# voltage_regulator_board.net
KiCad netlist of a schematic drawn in EAGLE
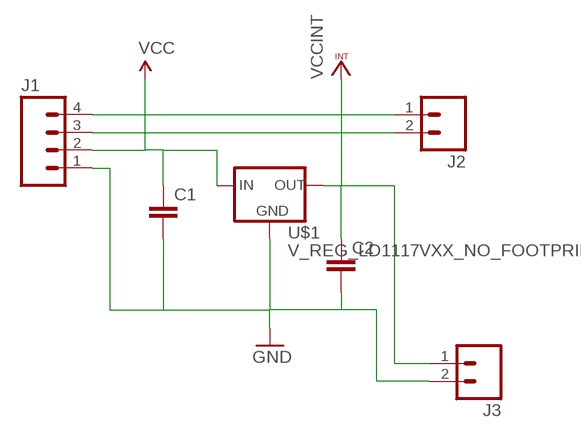
[diagram p0: schematic, sheet 1]

(export (version "E")
  (design (tool "Eeschema 10.0.6"))
  (components
    (comp (ref "C1")
      (value "CAP0805")
      (footprint "eagle-import:0805")
      (libsource (lib "eagle-import") (part "CAP0805"))
    )
    (comp (ref "C2")
      (value "CAP0805")
      (footprint "eagle-import:0805")
      (libsource (lib "eagle-import") (part "CAP0805"))
    )
    (comp (ref "J1")
      (value "M04LOCK")
      (footprint "eagle-import:1X04_LOCK")
      (libsource (lib "eagle-import") (part "M04LOCK"))
    )
    (comp (ref "J2")
      (value "M02LOCK")
      (footprint "eagle-import:1X02_LOCK")
      (libsource (lib "eagle-import") (part "M02LOCK"))
    )
    (comp (ref "J3")
      (value "M02LOCK")
      (footprint "eagle-import:1X02_LOCK")
      (libsource (lib "eagle-import") (part "M02LOCK"))
    )
    (comp (ref "U$1")
      (value "V_REG_LD1117VXX_NO_FOOTPRINT")
      (footprint "eagle-import:TO-220-NOFOOTPRINT")
      (libsource (lib "eagle-import") (part "V_REG_LD1117VXX_NO_FOOTPRINT"))
    )
  )
  (nets
    (net (code "1") (name "GND") (class "Default")
      (node (ref "C1") (pin "2") (pinfunction "2_2") (pintype "passive"))
      (node (ref "C2") (pin "2") (pinfunction "2_2") (pintype "passive"))
      (node (ref "J1") (pin "1") (pinfunction "1_1") (pintype "passive"))
      (node (ref "J3") (pin "2") (pinfunction "2_2") (pintype "passive"))
      (node (ref "U$1") (pin "GND") (pinfunction "GND_GND") (pintype "input"))
    )
    (net (code "2") (name "Net-(J1-Pad3)") (class "Default")
      (node (ref "J1") (pin "3") (pinfunction "3_3") (pintype "passive"))
      (node (ref "J2") (pin "2") (pinfunction "2_2") (pintype "passive"))
    )
    (net (code "3") (name "Net-(J1-Pad4)") (class "Default")
      (node (ref "J1") (pin "4") (pinfunction "4_4") (pintype "passive"))
      (node (ref "J2") (pin "1") (pinfunction "1_1") (pintype "passive"))
    )
    (net (code "4") (name "VCC") (class "Default")
      (node (ref "C1") (pin "1") (pinfunction "1_1") (pintype "passive"))
      (node (ref "J1") (pin "2") (pinfunction "2_2") (pintype "passive"))
      (node (ref "U$1") (pin "IN") (pinfunction "IN_IN") (pintype "input"))
    )
    (net (code "5") (name "VCCINT") (class "Default")
      (node (ref "C2") (pin "1") (pinfunction "1_1") (pintype "passive"))
      (node (ref "J3") (pin "1") (pinfunction "1_1") (pintype "passive"))
      (node (ref "U$1") (pin "OUT") (pinfunction "OUT_OUT") (pintype "passive"))
    )
  )
)
